# FE.net
KiCad netlist of a schematic drawn in Altium Designer
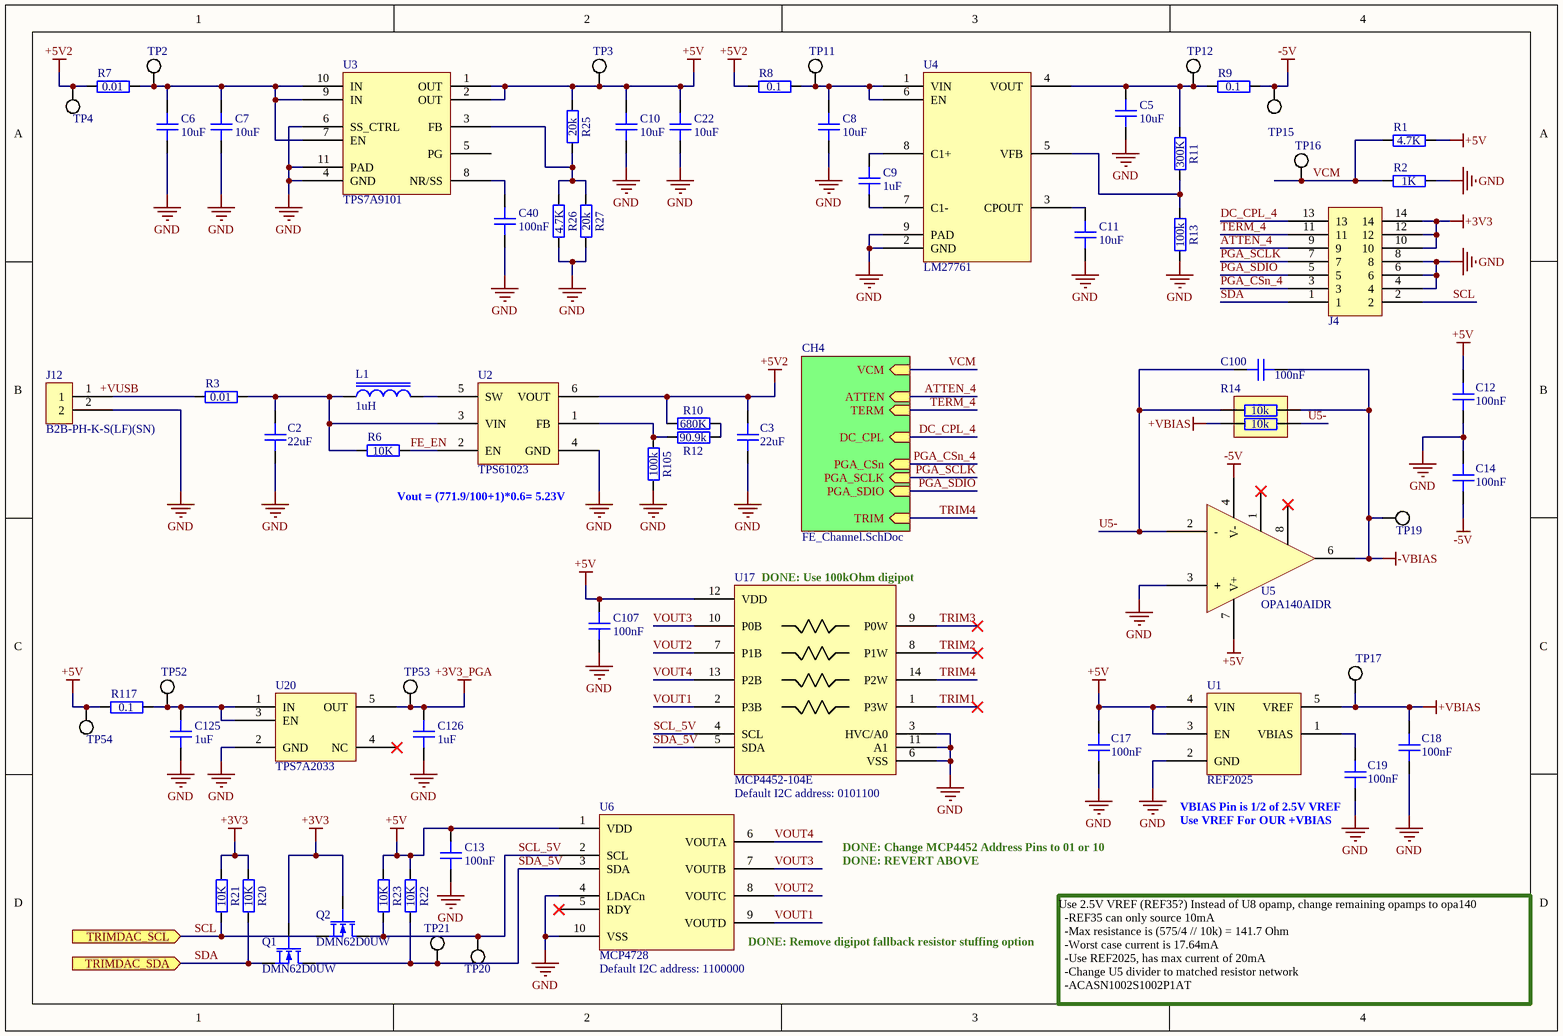
[diagram p0: FE.SchDoc]

(export (version "E")
  (design (tool "Eeschema 10.0.6"))
  (components
    (comp (ref "C2")
      (value "22uF")
      (footprint "GEN_C_0805")
      (fields
        (field (name "HOUSE PART NUMBER") "C-22uF-0805-002")
        (field (name "MANUFACTURER") "Murata")
        (field (name "MANUFACTURER PART NUMBER") "GRM21BR61E226ME44L")
      )
      (libsource (lib "DSO") (part "CAP 22uF 25V X5R 0805"))
    )
    (comp (ref "C3")
      (value "22uF")
      (footprint "GEN_C_0805")
      (fields
        (field (name "HOUSE PART NUMBER") "C-22uF-0805-002")
        (field (name "MANUFACTURER") "Murata")
        (field (name "MANUFACTURER PART NUMBER") "GRM21BR61E226ME44L")
      )
      (libsource (lib "DSO") (part "CAP 22uF 25V X5R 0805"))
    )
    (comp (ref "C5")
      (value "10uF")
      (footprint "GEN_C_0603")
      (fields
        (field (name "HOUSE PART NUMBER") "C-10uF-0603-002")
        (field (name "MANUFACTURER") "Murata")
        (field (name "MANUFACTURER PART NUMBER") "GRM188R61A106ME69D")
      )
      (libsource (lib "DSO") (part "CAP 10uF 10V X5R 0603"))
    )
    (comp (ref "C6")
      (value "10uF")
      (footprint "GEN_C_0603")
      (fields
        (field (name "HOUSE PART NUMBER") "C-10uF-0603-002")
        (field (name "MANUFACTURER") "Murata")
        (field (name "MANUFACTURER PART NUMBER") "GRM188R61A106ME69D")
      )
      (libsource (lib "DSO") (part "CAP 10uF 10V X5R 0603"))
    )
    (comp (ref "C7")
      (value "10uF")
      (footprint "GEN_C_0603")
      (fields
        (field (name "HOUSE PART NUMBER") "C-10uF-0603-002")
        (field (name "MANUFACTURER") "Murata")
        (field (name "MANUFACTURER PART NUMBER") "GRM188R61A106ME69D")
      )
      (libsource (lib "DSO") (part "CAP 10uF 10V X5R 0603"))
    )
    (comp (ref "C8")
      (value "10uF")
      (footprint "GEN_C_0603")
      (fields
        (field (name "HOUSE PART NUMBER") "C-10uF-0603-002")
        (field (name "MANUFACTURER") "Murata")
        (field (name "MANUFACTURER PART NUMBER") "GRM188R61A106ME69D")
      )
      (libsource (lib "DSO") (part "CAP 10uF 10V X5R 0603"))
    )
    (comp (ref "C9")
      (value "1uF")
      (footprint "GEN_C_0402")
      (fields
        (field (name "MANUFACTURER") "Murata")
        (field (name "MANUFACTURER PART NUMBER") "GRM155R61E105KA12D")
      )
      (libsource (lib "DSO") (part "CAP 1uF 25V X5R 0402"))
    )
    (comp (ref "C10")
      (value "10uF")
      (footprint "GEN_C_0603")
      (fields
        (field (name "HOUSE PART NUMBER") "C-10uF-0603-002")
        (field (name "MANUFACTURER") "Murata")
        (field (name "MANUFACTURER PART NUMBER") "GRM188R61A106ME69D")
      )
      (libsource (lib "DSO") (part "CAP 10uF 10V X5R 0603"))
    )
    (comp (ref "C11")
      (value "10uF")
      (footprint "GEN_C_0603")
      (fields
        (field (name "HOUSE PART NUMBER") "C-10uF-0603-002")
        (field (name "MANUFACTURER") "Murata")
        (field (name "MANUFACTURER PART NUMBER") "GRM188R61A106ME69D")
      )
      (libsource (lib "DSO") (part "CAP 10uF 10V X5R 0603"))
    )
    (comp (ref "C12")
      (value "100nF")
      (footprint "GEN_C_0402")
      (fields
        (field (name "HOUSE PART NUMBER") "C-100nF-0402-002")
        (field (name "MANUFACTURER") "Murata")
        (field (name "MANUFACTURER PART NUMBER") "GCM155R71C104KA55D")
      )
      (libsource (lib "DSO") (part "CAP 100nF 16V X7R 0402"))
    )
    (comp (ref "C13")
      (value "100nF")
      (footprint "GEN_C_0402")
      (fields
        (field (name "HOUSE PART NUMBER") "C-100nF-0402-002")
        (field (name "MANUFACTURER") "Murata")
        (field (name "MANUFACTURER PART NUMBER") "GCM155R71C104KA55D")
      )
      (libsource (lib "DSO") (part "CAP 100nF 16V X7R 0402"))
    )
    (comp (ref "C14")
      (value "100nF")
      (footprint "GEN_C_0402")
      (fields
        (field (name "HOUSE PART NUMBER") "C-100nF-0402-002")
        (field (name "MANUFACTURER") "Murata")
        (field (name "MANUFACTURER PART NUMBER") "GCM155R71C104KA55D")
      )
      (libsource (lib "DSO") (part "CAP 100nF 16V X7R 0402"))
    )
    (comp (ref "C17")
      (value "100nF")
      (footprint "GEN_C_0402")
      (fields
        (field (name "HOUSE PART NUMBER") "C-100nF-0402-002")
        (field (name "MANUFACTURER") "Murata")
        (field (name "MANUFACTURER PART NUMBER") "GCM155R71C104KA55D")
      )
      (libsource (lib "DSO") (part "CAP 100nF 16V X7R 0402"))
    )
    (comp (ref "C18")
      (value "100nF")
      (footprint "GEN_C_0402")
      (fields
        (field (name "HOUSE PART NUMBER") "C-100nF-0402-002")
        (field (name "MANUFACTURER") "Murata")
        (field (name "MANUFACTURER PART NUMBER") "GCM155R71C104KA55D")
      )
      (libsource (lib "DSO") (part "CAP 100nF 16V X7R 0402"))
    )
    (comp (ref "C19")
      (value "100nF")
      (footprint "GEN_C_0402")
      (fields
        (field (name "HOUSE PART NUMBER") "C-100nF-0402-002")
        (field (name "MANUFACTURER") "Murata")
        (field (name "MANUFACTURER PART NUMBER") "GCM155R71C104KA55D")
      )
      (libsource (lib "DSO") (part "CAP 100nF 16V X7R 0402"))
    )
    (comp (ref "C22")
      (value "10uF")
      (footprint "GEN_C_0603")
      (fields
        (field (name "HOUSE PART NUMBER") "C-10uF-0603-002")
        (field (name "MANUFACTURER") "Murata")
        (field (name "MANUFACTURER PART NUMBER") "GRM188R61A106ME69D")
      )
      (libsource (lib "DSO") (part "CAP 10uF 10V X5R 0603"))
    )
    (comp (ref "C40")
      (value "100nF")
      (footprint "GEN_C_0402")
      (fields
        (field (name "MANUFACTURER") "Murata")
        (field (name "HOUSE PART NUMBER") "C-100nF-0402-002")
        (field (name "MANUFACTURER PART NUMBER") "GCM155R71C104KA55D")
      )
      (libsource (lib "DSO") (part "CAP 100nF 16V X7R 0402"))
    )
    (comp (ref "C100")
      (value "100nF")
      (footprint "GEN_C_0402")
      (fields
        (field (name "HOUSE PART NUMBER") "C-100nF-0402-002")
        (field (name "MANUFACTURER") "Murata")
        (field (name "MANUFACTURER PART NUMBER") "GCM155R71C104KA55D")
      )
      (libsource (lib "DSO") (part "CAP 100nF 16V X7R 0402"))
    )
    (comp (ref "C107")
      (value "100nF")
      (footprint "GEN_C_0402")
      (fields
        (field (name "HOUSE PART NUMBER") "C-100nF-0402-002")
        (field (name "MANUFACTURER") "Murata")
        (field (name "MANUFACTURER PART NUMBER") "GCM155R71C104KA55D")
      )
      (libsource (lib "DSO") (part "CAP 100nF 16V X7R 0402"))
    )
    (comp (ref "C125")
      (value "1uF")
      (footprint "GEN_C_0402")
      (fields
        (field (name "MANUFACTURER") "Murata")
        (field (name "MANUFACTURER PART NUMBER") "GRM155R61E105KA12D")
      )
      (libsource (lib "DSO") (part "CAP 1uF 25V X5R 0402"))
    )
    (comp (ref "C126")
      (value "1uF")
      (footprint "GEN_C_0402")
      (fields
        (field (name "MANUFACTURER") "Murata")
        (field (name "MANUFACTURER PART NUMBER") "GRM155R61E105KA12D")
      )
      (libsource (lib "DSO") (part "CAP 1uF 25V X5R 0402"))
    )
    (comp (ref "J4")
      (value "2.54mm 2X7 Pin TH")
      (footprint "GEN_2.54mm_2X7_Pin_TH_RA")
      (libsource (lib "DSO") (part "CONN 2.54mm 2X7 Pin TH RA"))
    )
    (comp (ref "J12")
      (value "B2B-PH-K-S(LF)(SN)")
      (footprint "JST_B2B-PH-K-S(LF)(SN)")
      (fields
        (field (name "MANUFACTURER") "JST")
        (field (name "MANUFACTURER PART NUMBER") "B2B-PH-K-S-LF-SN")
      )
      (libsource (lib "DSO") (part "CONN JST PH 2 Pin TH"))
    )
    (comp (ref "L1")
      (value "1uH")
      (footprint "GEN_L_1210")
      (fields
        (field (name "MANUFACTURER") "Murata")
        (field (name "MANUFACTURER PART NUMBER") "1277AS-H-1R0M=P2")
      )
      (libsource (lib "DSO") (part "IND 1uH 3.1A 45 MOHM 1210"))
    )
    (comp (ref "Q1")
      (value "DMN62D0UW")
      (footprint "GEN_SOT_323")
      (fields (field (name "HOUSE PART NUMBER") "DMN62D0UW-7") (field (name "MANUFACTURER") "Diodes"))
      (libsource (lib "DSO") (part "NMOS DMN62D0UW"))
    )
    (comp (ref "Q2")
      (value "DMN62D0UW")
      (footprint "GEN_SOT_323")
      (fields (field (name "HOUSE PART NUMBER") "DMN62D0UW-7") (field (name "MANUFACTURER") "Diodes"))
      (libsource (lib "DSO") (part "NMOS DMN62D0UW"))
    )
    (comp (ref "R1")
      (value "4.7K")
      (footprint "GEN_R_0402")
      (fields
        (field (name "TOLERANCE") "1%")
        (field (name "MANUFACTURER") "Panasonic")
        (field (name "MANUFACTURER PART NUMBER") "ERJ-2RKF4701X")
      )
      (libsource (lib "DSO") (part "RES 4.7K OHM 1% 1/10W 0402"))
    )
    (comp (ref "R2")
      (value "1K")
      (footprint "GEN_R_0402")
      (fields
        (field (name "TOLERANCE") "1%")
        (field (name "MANUFACTURER") "Yageo")
        (field (name "HOUSE PART NUMBER") "R-1K-0402-1%-001")
      )
      (libsource (lib "DSO") (part "RES 1K OHM 1% 1/10W 0402"))
    )
    (comp (ref "R3")
      (value "0.01")
      (footprint "GEN_R_0603")
      (fields
        (field (name "TOLERANCE") "1%")
        (field (name "HOUSE PART NUMBER") "R-0.01-0603-1%-001")
        (field (name "MANUFACTURER") "Susumu")
      )
      (libsource (lib "DSO") (part "RES 0.01 OHM 1% 1/4W 0603"))
    )
    (comp (ref "R6")
      (value "10K")
      (footprint "GEN_R_0402")
      (fields
        (field (name "TOLERANCE") "1%")
        (field (name "MANUFACTURER") "Panasonic")
        (field (name "MANUFACTURER PART NUMBER") "ERJ-2RKF1002X")
      )
      (libsource (lib "") (part "RES 10K OHM 1% 1/10W 0402_1"))
    )
    (comp (ref "R7")
      (value "0.01")
      (footprint "GEN_R_0603")
      (fields
        (field (name "TOLERANCE") "1%")
        (field (name "HOUSE PART NUMBER") "R-0.01-0603-1%-001")
        (field (name "MANUFACTURER") "Susumu")
      )
      (libsource (lib "") (part "RES 0.01 OHM 1% 1/4W 0603_1"))
    )
    (comp (ref "R8")
      (value "0.1")
      (footprint "GEN_R_0402")
      (fields
        (field (name "TOLERANCE") "1%")
        (field (name "MANUFACTURER") "Panasonic")
        (field (name "MANUFACTURER PART NUMBER") "ERJ-2BSFR10X")
      )
      (libsource (lib "DSO") (part "RES 0.1 OHM 1% 1/6W 0402"))
    )
    (comp (ref "R9")
      (value "0.1")
      (footprint "GEN_R_0402")
      (fields
        (field (name "TOLERANCE") "1%")
        (field (name "MANUFACTURER") "Panasonic")
        (field (name "MANUFACTURER PART NUMBER") "ERJ-2BSFR10X")
      )
      (libsource (lib "DSO") (part "RES 0.1 OHM 1% 1/6W 0402"))
    )
    (comp (ref "R10")
      (value "680K")
      (footprint "GEN_R_0402")
      (fields
        (field (name "TOLERANCE") "1%")
        (field (name "MANUFACTURER") "Yageo")
        (field (name "MANUFACTURER PART NUMBER") "RC0402FR-07681KL")
      )
      (libsource (lib "DSO") (part "RES 680K OHM 1% 1/16W 0402"))
    )
    (comp (ref "R11")
      (value "300K")
      (footprint "GEN_R_0402")
      (fields
        (field (name "TOLERANCE") "1%")
        (field (name "MANUFACTURER") "Panasonic")
        (field (name "MANUFACTURER PART NUMBER") "ERJ-2RKF3003X")
      )
      (libsource (lib "DSO") (part "RES 300K OHM 1% 1/10W 0402"))
    )
    (comp (ref "R12")
      (value "90.9k")
      (footprint "GEN_R_0402")
      (fields
        (field (name "TOLERANCE") "1%")
        (field (name "MANUFACTURER") "Yageo")
        (field (name "MANUFACTURER PART NUMBER") "RC0402FR-0790K9L")
      )
      (libsource (lib "DSO") (part "RES 90.9K OHM 1% 1/16W 0402"))
    )
    (comp (ref "R13")
      (value "100k")
      (footprint "GEN_R_0402")
      (fields
        (field (name "TOLERANCE") "1%")
        (field (name "HOUSE PART NUMBER") "R-100K-0402-1%-001")
        (field (name "MANUFACTURER") "Yageo")
      )
      (libsource (lib "DSO") (part "RES 100K OHM 1% 1/10W 0402"))
    )
    (comp (ref "R14")
      (value "10K")
      (footprint "GEN_R_2ARRAY_0606")
      (fields
        (field (name "TOLERANCE") "1%")
        (field (name "MANUFACTURER") "Vishay Beyschlag")
        (field (name "MANUFACTURER PART NUMBER") "ACASN1002S1002P1ATF1002X")
      )
      (libsource (lib "DSO") (part "RES ARRAY 2x 10K OHM 0.05% 0606"))
    )
    (comp (ref "R20")
      (value "10K")
      (footprint "GEN_R_0402")
      (fields
        (field (name "TOLERANCE") "1%")
        (field (name "MANUFACTURER") "Panasonic")
        (field (name "MANUFACTURER PART NUMBER") "ERJ-2RKF1002X")
      )
      (libsource (lib "DSO") (part "RES 10K OHM 1% 1/10W 0402"))
    )
    (comp (ref "R21")
      (value "10K")
      (footprint "GEN_R_0402")
      (fields
        (field (name "TOLERANCE") "1%")
        (field (name "MANUFACTURER") "Panasonic")
        (field (name "MANUFACTURER PART NUMBER") "ERJ-2RKF1002X")
      )
      (libsource (lib "DSO") (part "RES 10K OHM 1% 1/10W 0402"))
    )
    (comp (ref "R22")
      (value "10K")
      (footprint "GEN_R_0402")
      (fields
        (field (name "TOLERANCE") "1%")
        (field (name "MANUFACTURER") "Panasonic")
        (field (name "MANUFACTURER PART NUMBER") "ERJ-2RKF1002X")
      )
      (libsource (lib "DSO") (part "RES 10K OHM 1% 1/10W 0402"))
    )
    (comp (ref "R23")
      (value "10K")
      (footprint "GEN_R_0402")
      (fields
        (field (name "TOLERANCE") "1%")
        (field (name "MANUFACTURER") "Panasonic")
        (field (name "MANUFACTURER PART NUMBER") "ERJ-2RKF1002X")
      )
      (libsource (lib "DSO") (part "RES 10K OHM 1% 1/10W 0402"))
    )
    (comp (ref "R25")
      (value "20k")
      (footprint "GEN_R_0402")
      (fields
        (field (name "TOLERANCE") "1%")
        (field (name "MANUFACTURER") "Yageo")
        (field (name "MANUFACTURER PART NUMBER") "RC0402FR-0720KL")
      )
      (libsource (lib "DSO") (part "RES 20K OHM 1% 1/16W 0402"))
    )
    (comp (ref "R26")
      (value "4.7K")
      (footprint "GEN_R_0402")
      (fields
        (field (name "TOLERANCE") "1%")
        (field (name "MANUFACTURER") "Panasonic")
        (field (name "MANUFACTURER PART NUMBER") "ERJ-2RKF4701X")
      )
      (libsource (lib "DSO") (part "RES 4.7K OHM 1% 1/10W 0402"))
    )
    (comp (ref "R27")
      (value "20k")
      (footprint "GEN_R_0402")
      (fields
        (field (name "TOLERANCE") "1%")
        (field (name "MANUFACTURER") "Yageo")
        (field (name "MANUFACTURER PART NUMBER") "RC0402FR-0720KL")
      )
      (libsource (lib "DSO") (part "RES 20K OHM 1% 1/16W 0402"))
    )
    (comp (ref "R105")
      (value "100k")
      (footprint "GEN_R_0402")
      (fields
        (field (name "TOLERANCE") "1%")
        (field (name "HOUSE PART NUMBER") "R-100K-0402-1%-001")
        (field (name "MANUFACTURER") "Yageo")
      )
      (libsource (lib "DSO") (part "RES 100K OHM 1% 1/10W 0402"))
    )
    (comp (ref "R117")
      (value "0.1")
      (footprint "GEN_R_0402")
      (fields
        (field (name "TOLERANCE") "1%")
        (field (name "MANUFACTURER") "Panasonic")
        (field (name "MANUFACTURER PART NUMBER") "ERJ-2BSFR10X")
      )
      (libsource (lib "DSO") (part "RES 0.1 OHM 1% 1/6W 0402"))
    )
    (comp (ref "TP2") (value "PCB") (footprint "GEN_TP_PCB") (libsource (lib "DSO") (part "TP PCB 1mm")))
    (comp (ref "TP3") (value "PCB") (footprint "GEN_TP_PCB") (libsource (lib "DSO") (part "TP PCB 1mm")))
    (comp (ref "TP4") (value "PCB") (footprint "GEN_TP_PCB") (libsource (lib "DSO") (part "TP PCB 1mm")))
    (comp (ref "TP11") (value "PCB") (footprint "GEN_TP_PCB") (libsource (lib "DSO") (part "TP PCB 1mm")))
    (comp (ref "TP12") (value "PCB") (footprint "GEN_TP_PCB") (libsource (lib "DSO") (part "TP PCB 1mm")))
    (comp (ref "TP15") (value "PCB") (footprint "GEN_TP_PCB") (libsource (lib "DSO") (part "TP PCB 1mm")))
    (comp (ref "TP16") (value "PCB") (footprint "GEN_TP_PCB") (libsource (lib "DSO") (part "TP PCB 1mm")))
    (comp (ref "TP17") (value "PCB") (footprint "GEN_TP_PCB") (libsource (lib "DSO") (part "TP PCB 1mm")))
    (comp (ref "TP19") (value "PCB") (footprint "GEN_TP_PCB") (libsource (lib "DSO") (part "TP PCB 1mm")))
    (comp (ref "TP20") (value "PCB") (footprint "GEN_TP_PCB") (libsource (lib "DSO") (part "TP PCB 1mm")))
    (comp (ref "TP21") (value "PCB") (footprint "GEN_TP_PCB") (libsource (lib "DSO") (part "TP PCB 1mm")))
    (comp (ref "TP52") (value "PCB") (footprint "GEN_TP_PCB") (libsource (lib "DSO") (part "TP PCB 1mm")))
    (comp (ref "TP53") (value "PCB") (footprint "GEN_TP_PCB") (libsource (lib "DSO") (part "TP PCB 1mm")))
    (comp (ref "TP54") (value "PCB") (footprint "GEN_TP_PCB") (libsource (lib "DSO") (part "TP PCB 1mm")))
    (comp (ref "U1")
      (value "REF2025")
      (footprint "GEN_SOT23_5_950_2900X1600X1450")
      (libsource (lib "DSO") (part "IC VREF REF2025"))
    )
    (comp (ref "U2")
      (value "TPS61023")
      (footprint "TI_SOT563_DRL0006A")
      (fields
        (field (name "MANUFACTURER") "Texas Instruments")
        (field (name "MANUFACTURER PART NUMBER") "TPS61023DRLT")
      )
      (libsource (lib "DSO") (part "IC BOOST TPS61023"))
    )
    (comp (ref "U3")
      (value "TPS7A9101")
      (footprint "TI_WSON10_DSK0010A")
      (fields
        (field (name "MANUFACTURER") "Texas Instruments")
        (field (name "MANUFACTURER PART NUMBER") "TPS7A9101DSKR")
      )
      (libsource (lib "DSO") (part "IC LDO TPS7A9101"))
    )
    (comp (ref "U4")
      (value "LM27761")
      (footprint "TI_WSON8_DSG0008A")
      (fields
        (field (name "MANUFACTURER") "Texas Instruments")
        (field (name "MANUFACTURER PART NUMBER") "LM27761DSGR")
      )
      (libsource (lib "DSO") (part "IC CPUMP LM27761"))
    )
    (comp (ref "U5")
      (value "OPA140AIDR")
      (footprint "TI_SOIC8_D0008A")
      (fields (field (name "MANUFACTURER") "Texas Instruments"))
      (libsource (lib "DSO") (part "IC OPAMP OPA140"))
    )
    (comp (ref "U6")
      (value "MCP4728")
      (footprint "MC_MSOP10_UN")
      (fields (field (name "MANUFACTURER") "Microchip"))
      (libsource (lib "DSO") (part "IC DAC QUAD MCP4728"))
    )
    (comp (ref "U17")
      (value "MCP4452-104E")
      (footprint "MC_TSSOP14")
      (fields (field (name "MANUFACTURER") "Microchip"))
      (libsource (lib "DSO") (part "IC DIGIPOT QUAD MCP4452-104E"))
    )
    (comp (ref "U20")
      (value "TPS7A2033")
      (footprint "GEN_SOT23_5_950_2900X1600X1450")
      (fields
        (field (name "MANUFACTURER") "Texas Instruments")
        (field (name "MANUFACTURER PART NUMBER") "TPS7A2033PDBVR")
      )
      (libsource (lib "DSO") (part "IC LDO TPS7A2033"))
    )
  )
  (nets
    (net (code "1") (name "+3V3") (class "Default")
      (node (ref "J4") (pin "10") (pinfunction "10_10") (pintype "passive"))
      (node (ref "J4") (pin "12") (pinfunction "12_12") (pintype "passive"))
      (node (ref "J4") (pin "14") (pinfunction "14_14") (pintype "passive"))
      (node (ref "Q1") (pin "2") (pinfunction "G_2") (pintype "passive"))
      (node (ref "Q2") (pin "2") (pinfunction "G_2") (pintype "passive"))
      (node (ref "R20") (pin "2") (pinfunction "2_2") (pintype "passive"))
      (node (ref "R21") (pin "2") (pinfunction "2_2") (pintype "passive"))
    )
    (net (code "2") (name "+3V3_PGA") (class "Default")
      (node (ref "C126") (pin "2") (pinfunction "2_2") (pintype "passive"))
      (node (ref "TP53") (pin "1") (pinfunction "1_1") (pintype "passive"))
      (node (ref "U20") (pin "5") (pinfunction "OUT_5") (pintype "power_in"))
    )
    (net (code "3") (name "+5V") (class "Default")
      (node (ref "C10") (pin "2") (pinfunction "2_2") (pintype "passive"))
      (node (ref "C107") (pin "2") (pinfunction "2_2") (pintype "passive"))
      (node (ref "C12") (pin "1") (pinfunction "1_1") (pintype "passive"))
      (node (ref "C13") (pin "2") (pinfunction "2_2") (pintype "passive"))
      (node (ref "C17") (pin "1") (pinfunction "1_1") (pintype "passive"))
      (node (ref "C22") (pin "2") (pinfunction "2_2") (pintype "passive"))
      (node (ref "R1") (pin "2") (pinfunction "2_2") (pintype "passive"))
      (node (ref "R117") (pin "1") (pinfunction "1_1") (pintype "passive"))
      (node (ref "R22") (pin "2") (pinfunction "2_2") (pintype "passive"))
      (node (ref "R23") (pin "2") (pinfunction "2_2") (pintype "passive"))
      (node (ref "R25") (pin "2") (pinfunction "2_2") (pintype "passive"))
      (node (ref "TP3") (pin "1") (pinfunction "1_1") (pintype "passive"))
      (node (ref "TP54") (pin "1") (pinfunction "1_1") (pintype "passive"))
      (node (ref "U1") (pin "3") (pinfunction "EN_3") (pintype "passive"))
      (node (ref "U1") (pin "4") (pinfunction "VIN_4") (pintype "passive"))
      (node (ref "U17") (pin "12") (pinfunction "VDD_12") (pintype "power_in"))
      (node (ref "U3") (pin "1") (pinfunction "OUT_1") (pintype "power_in"))
      (node (ref "U3") (pin "2") (pinfunction "OUT_2") (pintype "power_in"))
      (node (ref "U5") (pin "7") (pinfunction "V+_7") (pintype "passive"))
      (node (ref "U6") (pin "1") (pinfunction "VDD_1") (pintype "power_in"))
    )
    (net (code "4") (name "+5V2") (class "Default")
      (node (ref "C3") (pin "2") (pinfunction "2_2") (pintype "passive"))
      (node (ref "R10") (pin "2") (pinfunction "2_2") (pintype "passive"))
      (node (ref "R7") (pin "1") (pinfunction "1_1") (pintype "passive"))
      (node (ref "R8") (pin "1") (pinfunction "1_1") (pintype "passive"))
      (node (ref "TP4") (pin "1") (pinfunction "1_1") (pintype "passive"))
      (node (ref "U2") (pin "6") (pinfunction "VOUT_6") (pintype "passive"))
    )
    (net (code "5") (name "+VBIAS") (class "Default")
      (node (ref "C18") (pin "1") (pinfunction "1_1") (pintype "passive"))
      (node (ref "R14") (pin "2") (pinfunction "2_2") (pintype "passive"))
      (node (ref "TP17") (pin "1") (pinfunction "1_1") (pintype "passive"))
      (node (ref "U1") (pin "5") (pinfunction "VREF_5") (pintype "passive"))
    )
    (net (code "6") (name "-5V") (class "Default")
      (node (ref "C14") (pin "2") (pinfunction "2_2") (pintype "passive"))
      (node (ref "R9") (pin "2") (pinfunction "2_2") (pintype "passive"))
      (node (ref "TP15") (pin "1") (pinfunction "1_1") (pintype "passive"))
      (node (ref "U5") (pin "4") (pinfunction "V-_4") (pintype "passive"))
    )
    (net (code "7") (name "-VBIAS") (class "Default")
      (node (ref "C100") (pin "1") (pinfunction "1_1") (pintype "passive"))
      (node (ref "R14") (pin "4") (pinfunction "4_4") (pintype "passive"))
      (node (ref "TP19") (pin "1") (pinfunction "1_1") (pintype "passive"))
      (node (ref "U5") (pin "6") (pinfunction "OUT_6") (pintype "passive"))
    )
    (net (code "8") (name "/+VUSB") (class "Default")
      (node (ref "J12") (pin "1") (pinfunction "1_1") (pintype "passive"))
      (node (ref "R3") (pin "2") (pinfunction "2_2") (pintype "passive"))
    )
    (net (code "9") (name "/ATTEN_4") (class "Default")
      (node (ref "J4") (pin "9") (pinfunction "9_9") (pintype "passive"))
    )
    (net (code "10") (name "/DC_CPL_4") (class "Default")
      (node (ref "J4") (pin "13") (pinfunction "13_13") (pintype "passive"))
    )
    (net (code "11") (name "/FE_EN") (class "Default")
      (node (ref "R6") (pin "1") (pinfunction "1_1") (pintype "passive"))
      (node (ref "U2") (pin "2") (pinfunction "EN_2") (pintype "passive"))
    )
    (net (code "12") (name "/PGA_CSn_4") (class "Default")
      (node (ref "J4") (pin "3") (pinfunction "3_3") (pintype "passive"))
    )
    (net (code "13") (name "/PGA_SCLK") (class "Default")
      (node (ref "J4") (pin "7") (pinfunction "7_7") (pintype "passive"))
    )
    (net (code "14") (name "/PGA_SDIO") (class "Default")
      (node (ref "J4") (pin "5") (pinfunction "5_5") (pintype "passive"))
    )
    (net (code "15") (name "/SCL") (class "Default")
      (node (ref "J4") (pin "2") (pinfunction "2_2") (pintype "passive"))
      (node (ref "Q2") (pin "3") (pinfunction "S_3") (pintype "passive"))
      (node (ref "R21") (pin "1") (pinfunction "1_1") (pintype "passive"))
    )
    (net (code "16") (name "/SCL_5V") (class "Default")
      (node (ref "Q2") (pin "1") (pinfunction "D_1") (pintype "passive"))
      (node (ref "R23") (pin "1") (pinfunction "1_1") (pintype "passive"))
      (node (ref "TP20") (pin "1") (pinfunction "1_1") (pintype "passive"))
      (node (ref "U17") (pin "4") (pinfunction "SCL_4") (pintype "passive"))
      (node (ref "U6") (pin "2") (pinfunction "SCL_2") (pintype "passive"))
    )
    (net (code "17") (name "/SDA") (class "Default")
      (node (ref "J4") (pin "1") (pinfunction "1_1") (pintype "passive"))
      (node (ref "Q1") (pin "3") (pinfunction "S_3") (pintype "passive"))
      (node (ref "R20") (pin "1") (pinfunction "1_1") (pintype "passive"))
    )
    (net (code "18") (name "/SDA_5V") (class "Default")
      (node (ref "Q1") (pin "1") (pinfunction "D_1") (pintype "passive"))
      (node (ref "R22") (pin "1") (pinfunction "1_1") (pintype "passive"))
      (node (ref "TP21") (pin "1") (pinfunction "1_1") (pintype "passive"))
      (node (ref "U17") (pin "5") (pinfunction "SDA_5") (pintype "passive"))
      (node (ref "U6") (pin "3") (pinfunction "SDA_3") (pintype "passive"))
    )
    (net (code "19") (name "/TERM_4") (class "Default")
      (node (ref "J4") (pin "11") (pinfunction "11_11") (pintype "passive"))
    )
    (net (code "20") (name "/TRIM1") (class "Default")
      (node (ref "U17") (pin "1") (pinfunction "P3W_1") (pintype "passive+no_connect"))
    )
    (net (code "21") (name "/TRIM2") (class "Default")
      (node (ref "U17") (pin "8") (pinfunction "P1W_8") (pintype "passive+no_connect"))
    )
    (net (code "22") (name "/TRIM3") (class "Default")
      (node (ref "U17") (pin "9") (pinfunction "P0W_9") (pintype "passive+no_connect"))
    )
    (net (code "23") (name "/TRIM4") (class "Default")
      (node (ref "U17") (pin "14") (pinfunction "P2W_14") (pintype "passive"))
    )
    (net (code "24") (name "/U5-") (class "Default")
      (node (ref "C100") (pin "2") (pinfunction "2_2") (pintype "passive"))
      (node (ref "R14") (pin "1") (pinfunction "1_1") (pintype "passive"))
      (node (ref "R14") (pin "3") (pinfunction "3_3") (pintype "passive"))
      (node (ref "U5") (pin "2") (pinfunction "-_2") (pintype "passive"))
    )
    (net (code "25") (name "/VCM") (class "Default")
      (node (ref "R1") (pin "1") (pinfunction "1_1") (pintype "passive"))
      (node (ref "R2") (pin "1") (pinfunction "1_1") (pintype "passive"))
      (node (ref "TP16") (pin "1") (pinfunction "1_1") (pintype "passive"))
    )
    (net (code "26") (name "/VOUT1") (class "Default")
      (node (ref "U17") (pin "2") (pinfunction "P3B_2") (pintype "passive"))
      (node (ref "U6") (pin "9") (pinfunction "VOUTD_9") (pintype "passive"))
    )
    (net (code "27") (name "/VOUT2") (class "Default")
      (node (ref "U17") (pin "7") (pinfunction "P1B_7") (pintype "passive"))
      (node (ref "U6") (pin "8") (pinfunction "VOUTC_8") (pintype "passive"))
    )
    (net (code "28") (name "/VOUT3") (class "Default")
      (node (ref "U17") (pin "10") (pinfunction "P0B_10") (pintype "passive"))
      (node (ref "U6") (pin "7") (pinfunction "VOUTB_7") (pintype "passive"))
    )
    (net (code "29") (name "/VOUT4") (class "Default")
      (node (ref "U17") (pin "13") (pinfunction "P2B_13") (pintype "passive"))
      (node (ref "U6") (pin "6") (pinfunction "VOUTA_6") (pintype "passive"))
    )
    (net (code "30") (name "GND") (class "Default")
      (node (ref "C10") (pin "1") (pinfunction "1_1") (pintype "passive"))
      (node (ref "C107") (pin "1") (pinfunction "1_1") (pintype "passive"))
      (node (ref "C11") (pin "1") (pinfunction "1_1") (pintype "passive"))
      (node (ref "C12") (pin "2") (pinfunction "2_2") (pintype "passive"))
      (node (ref "C125") (pin "1") (pinfunction "1_1") (pintype "passive"))
      (node (ref "C126") (pin "1") (pinfunction "1_1") (pintype "passive"))
      (node (ref "C13") (pin "1") (pinfunction "1_1") (pintype "passive"))
      (node (ref "C14") (pin "1") (pinfunction "1_1") (pintype "passive"))
      (node (ref "C17") (pin "2") (pinfunction "2_2") (pintype "passive"))
      (node (ref "C18") (pin "2") (pinfunction "2_2") (pintype "passive"))
      (node (ref "C19") (pin "1") (pinfunction "1_1") (pintype "passive"))
      (node (ref "C2") (pin "1") (pinfunction "1_1") (pintype "passive"))
      (node (ref "C22") (pin "1") (pinfunction "1_1") (pintype "passive"))
      (node (ref "C3") (pin "1") (pinfunction "1_1") (pintype "passive"))
      (node (ref "C40") (pin "1") (pinfunction "1_1") (pintype "passive"))
      (node (ref "C5") (pin "1") (pinfunction "1_1") (pintype "passive"))
      (node (ref "C6") (pin "1") (pinfunction "1_1") (pintype "passive"))
      (node (ref "C7") (pin "1") (pinfunction "1_1") (pintype "passive"))
      (node (ref "C8") (pin "1") (pinfunction "1_1") (pintype "passive"))
      (node (ref "J12") (pin "2") (pinfunction "2_2") (pintype "passive"))
      (node (ref "J4") (pin "4") (pinfunction "4_4") (pintype "passive"))
      (node (ref "J4") (pin "6") (pinfunction "6_6") (pintype "passive"))
      (node (ref "J4") (pin "8") (pinfunction "8_8") (pintype "passive"))
      (node (ref "R105") (pin "1") (pinfunction "1_1") (pintype "passive"))
      (node (ref "R13") (pin "1") (pinfunction "1_1") (pintype "passive"))
      (node (ref "R2") (pin "2") (pinfunction "2_2") (pintype "passive"))
      (node (ref "R26") (pin "1") (pinfunction "1_1") (pintype "passive"))
      (node (ref "R27") (pin "1") (pinfunction "1_1") (pintype "passive"))
      (node (ref "U1") (pin "2") (pinfunction "GND_2") (pintype "passive"))
      (node (ref "U17") (pin "11") (pinfunction "A1_11") (pintype "passive"))
      (node (ref "U17") (pin "3") (pinfunction "HVC/A0_3") (pintype "passive"))
      (node (ref "U17") (pin "6") (pinfunction "VSS_6") (pintype "power_in"))
      (node (ref "U2") (pin "4") (pinfunction "GND_4") (pintype "power_in"))
      (node (ref "U20") (pin "2") (pinfunction "GND_2") (pintype "power_in"))
      (node (ref "U3") (pin "11") (pinfunction "PAD_11") (pintype "passive"))
      (node (ref "U3") (pin "4") (pinfunction "GND_4") (pintype "power_in"))
      (node (ref "U3") (pin "6") (pinfunction "SS_CTRL_6") (pintype "passive"))
      (node (ref "U4") (pin "2") (pinfunction "GND_2") (pintype "power_in"))
      (node (ref "U4") (pin "9") (pinfunction "PAD_9") (pintype "power_in"))
      (node (ref "U5") (pin "3") (pinfunction "+_3") (pintype "passive"))
      (node (ref "U6") (pin "10") (pinfunction "VSS_10") (pintype "power_in"))
      (node (ref "U6") (pin "4") (pinfunction "LDACn_4") (pintype "passive"))
    )
    (net (code "31") (name "Net-(R10-Pad1)") (class "Default")
      (node (ref "R10") (pin "1") (pinfunction "1_1") (pintype "passive"))
      (node (ref "R12") (pin "2") (pinfunction "2_2") (pintype "passive"))
    )
    (net (code "32") (name "Net-(U1-VBIAS)") (class "Default")
      (node (ref "C19") (pin "2") (pinfunction "2_2") (pintype "passive"))
      (node (ref "U1") (pin "1") (pinfunction "VBIAS_1") (pintype "power_in"))
    )
    (net (code "33") (name "Net-(U2-FB)") (class "Default")
      (node (ref "R105") (pin "2") (pinfunction "2_2") (pintype "passive"))
      (node (ref "R12") (pin "1") (pinfunction "1_1") (pintype "passive"))
      (node (ref "U2") (pin "1") (pinfunction "FB_1") (pintype "passive"))
    )
    (net (code "34") (name "Net-(U2-SW)") (class "Default")
      (node (ref "L1") (pin "2") (pinfunction "2_2") (pintype "passive"))
      (node (ref "U2") (pin "5") (pinfunction "SW_5") (pintype "passive"))
    )
    (net (code "35") (name "Net-(U2-VIN)") (class "Default")
      (node (ref "C2") (pin "2") (pinfunction "2_2") (pintype "passive"))
      (node (ref "L1") (pin "1") (pinfunction "1_1") (pintype "passive"))
      (node (ref "R3") (pin "1") (pinfunction "1_1") (pintype "passive"))
      (node (ref "R6") (pin "2") (pinfunction "2_2") (pintype "passive"))
      (node (ref "U2") (pin "3") (pinfunction "VIN_3") (pintype "power_in"))
    )
    (net (code "36") (name "Net-(U3-EN)") (class "Default")
      (node (ref "C6") (pin "2") (pinfunction "2_2") (pintype "passive"))
      (node (ref "C7") (pin "2") (pinfunction "2_2") (pintype "passive"))
      (node (ref "R7") (pin "2") (pinfunction "2_2") (pintype "passive"))
      (node (ref "TP2") (pin "1") (pinfunction "1_1") (pintype "passive"))
      (node (ref "U3") (pin "10") (pinfunction "IN_10") (pintype "power_in"))
      (node (ref "U3") (pin "7") (pinfunction "EN_7") (pintype "passive"))
      (node (ref "U3") (pin "9") (pinfunction "IN_9") (pintype "power_in"))
    )
    (net (code "37") (name "Net-(U3-FB)") (class "Default")
      (node (ref "R25") (pin "1") (pinfunction "1_1") (pintype "passive"))
      (node (ref "R26") (pin "2") (pinfunction "2_2") (pintype "passive"))
      (node (ref "R27") (pin "2") (pinfunction "2_2") (pintype "passive"))
      (node (ref "U3") (pin "3") (pinfunction "FB_3") (pintype "passive"))
    )
    (net (code "38") (name "Net-(U3-NR{slash}SS)") (class "Default")
      (node (ref "C40") (pin "2") (pinfunction "2_2") (pintype "passive"))
      (node (ref "U3") (pin "8") (pinfunction "NR/SS_8") (pintype "passive"))
    )
    (net (code "39") (name "Net-(U4-C1+)") (class "Default")
      (node (ref "C9") (pin "2") (pinfunction "2_2") (pintype "passive"))
      (node (ref "U4") (pin "8") (pinfunction "C1+_8") (pintype "passive"))
    )
    (net (code "40") (name "Net-(U4-C1-)") (class "Default")
      (node (ref "C9") (pin "1") (pinfunction "1_1") (pintype "passive"))
      (node (ref "U4") (pin "7") (pinfunction "C1-_7") (pintype "passive"))
    )
    (net (code "41") (name "Net-(U4-CPOUT)") (class "Default")
      (node (ref "C11") (pin "2") (pinfunction "2_2") (pintype "passive"))
      (node (ref "U4") (pin "3") (pinfunction "CPOUT_3") (pintype "passive"))
    )
    (net (code "42") (name "Net-(U4-EN)") (class "Default")
      (node (ref "C8") (pin "2") (pinfunction "2_2") (pintype "passive"))
      (node (ref "R8") (pin "2") (pinfunction "2_2") (pintype "passive"))
      (node (ref "TP11") (pin "1") (pinfunction "1_1") (pintype "passive"))
      (node (ref "U4") (pin "1") (pinfunction "VIN_1") (pintype "power_in"))
      (node (ref "U4") (pin "6") (pinfunction "EN_6") (pintype "passive"))
    )
    (net (code "43") (name "Net-(U4-VFB)") (class "Default")
      (node (ref "R11") (pin "1") (pinfunction "1_1") (pintype "passive"))
      (node (ref "R13") (pin "2") (pinfunction "2_2") (pintype "passive"))
      (node (ref "U4") (pin "5") (pinfunction "VFB_5") (pintype "passive"))
    )
    (net (code "44") (name "Net-(U4-VOUT)") (class "Default")
      (node (ref "C5") (pin "2") (pinfunction "2_2") (pintype "passive"))
      (node (ref "R11") (pin "2") (pinfunction "2_2") (pintype "passive"))
      (node (ref "R9") (pin "1") (pinfunction "1_1") (pintype "passive"))
      (node (ref "TP12") (pin "1") (pinfunction "1_1") (pintype "passive"))
      (node (ref "U4") (pin "4") (pinfunction "VOUT_4") (pintype "power_in"))
    )
    (net (code "45") (name "Net-(U20-EN)") (class "Default")
      (node (ref "C125") (pin "2") (pinfunction "2_2") (pintype "passive"))
      (node (ref "R117") (pin "2") (pinfunction "2_2") (pintype "passive"))
      (node (ref "TP52") (pin "1") (pinfunction "1_1") (pintype "passive"))
      (node (ref "U20") (pin "1") (pinfunction "IN_1") (pintype "power_in"))
      (node (ref "U20") (pin "3") (pinfunction "EN_3") (pintype "passive"))
    )
    (net (code "46") (name "unconnected-(U3-PG-Pad5)") (class "Default")
      (node (ref "U3") (pin "5") (pinfunction "PG_5") (pintype "passive"))
    )
    (net (code "47") (name "unconnected-(U5-N1-Pad1)") (class "Default")
      (node (ref "U5") (pin "1") (pinfunction "N1_1") (pintype "passive+no_connect"))
    )
    (net (code "48") (name "unconnected-(U5-N2-Pad8)") (class "Default")
      (node (ref "U5") (pin "8") (pinfunction "N2_8") (pintype "passive+no_connect"))
    )
    (net (code "49") (name "unconnected-(U6-RDY-Pad5)") (class "Default")
      (node (ref "U6") (pin "5") (pinfunction "RDY_5") (pintype "passive+no_connect"))
    )
    (net (code "50") (name "unconnected-(U20-NC-Pad4)") (class "Default")
      (node (ref "U20") (pin "4") (pinfunction "NC_4") (pintype "passive+no_connect"))
    )
  )
)
